# MCU_A_ESP32-WROOM-32U.net
KiCad netlist of a schematic drawn in Altium Designer
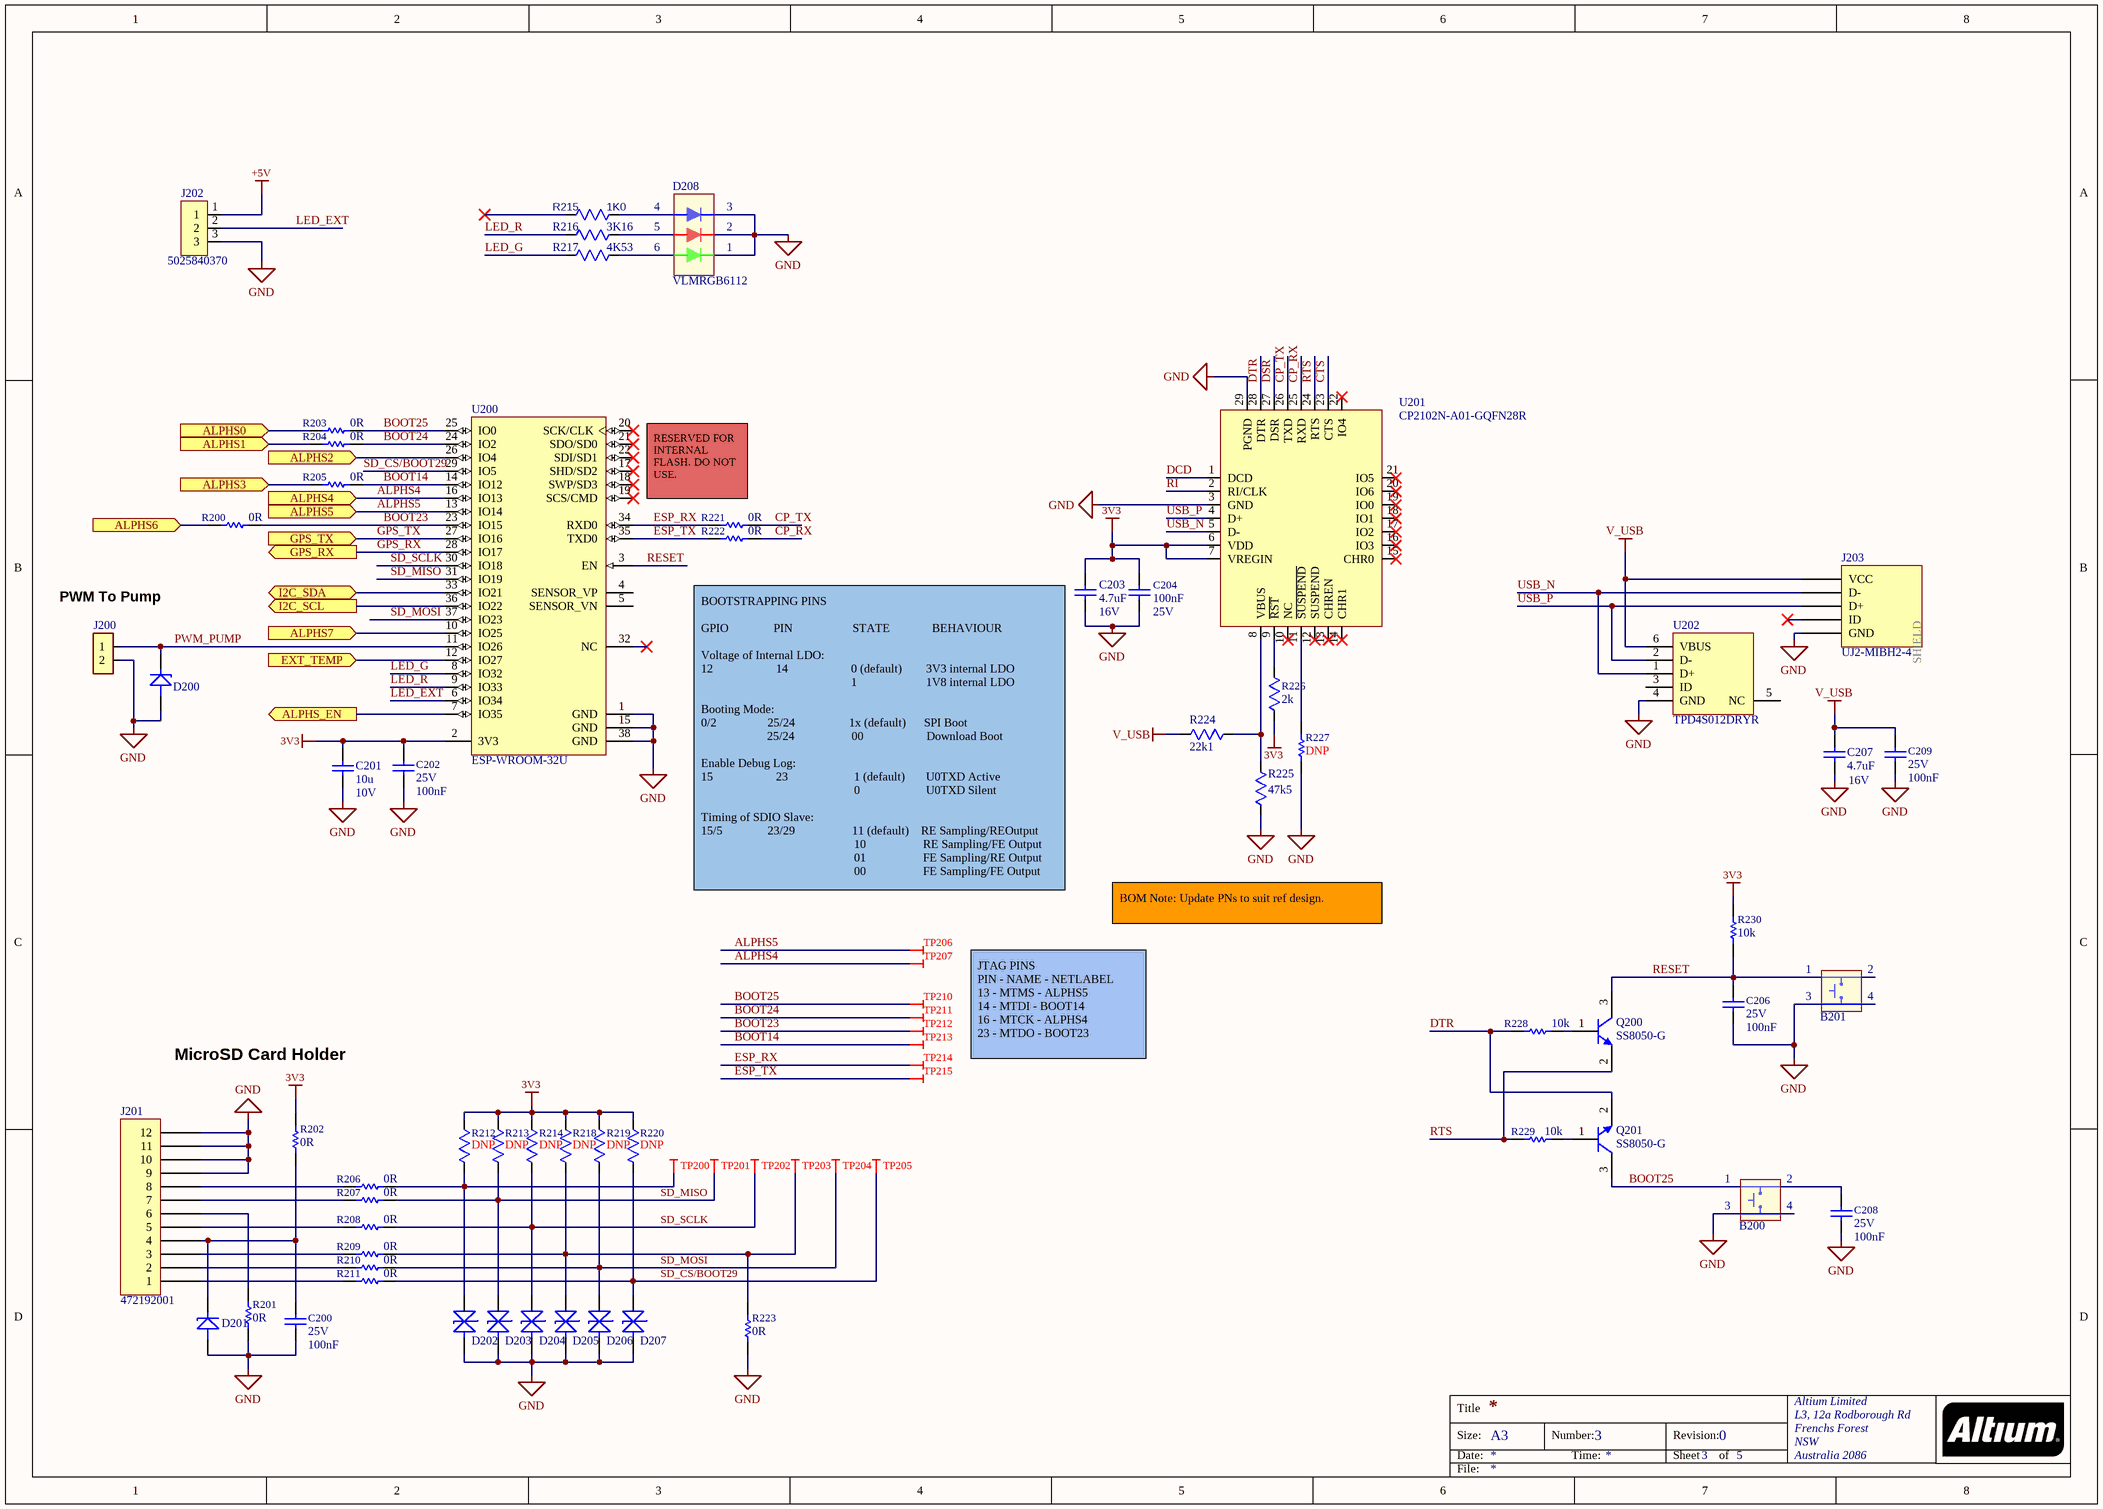
[diagram p0: MCU A ESP32-WROOM-32U.SchDoc]

(export (version "E")
  (design (tool "Eeschema 10.0.6"))
  (components
    (comp (ref "B200")
      (value "Button C&K PTS815 SJG 250 SMTR LFS")
      (footprint "PTS 815")
      (description "Push Button Top")
      (fields
        (field (name "MANUFACTURER") "C&K Components")
        (field (name "MANUFACTURER PART NUMBER") "PTS815 SJG 250 SMTR LFS")
      )
      (libsource (lib "Connectors") (part "Button C&K PTS815 SJG 250 SMTR LFS"))
    )
    (comp (ref "B201")
      (value "Button C&K PTS815 SJG 250 SMTR LFS")
      (footprint "PTS 815")
      (description "Push Button Top")
      (fields
        (field (name "MANUFACTURER") "C&K Components")
        (field (name "MANUFACTURER PART NUMBER") "PTS815 SJG 250 SMTR LFS")
      )
      (libsource (lib "Connectors") (part "Button C&K PTS815 SJG 250 SMTR LFS"))
    )
    (comp (ref "C200")
      (value "100nF")
      (footprint "CAPC1005X06N")
      (fields
        (field (name "VOLTAGE") "25V")
        (field (name "MANUFACTURER PART NUMBER") "CL05A104KA5NNNC")
        (field (name "MANUFACTURER") "Samsung")
        (field (name "Comment") "4.7uF")
      )
      (libsource (lib "Capacitors") (part "4.7uF_0603_10V"))
    )
    (comp (ref "C201")
      (value "10u")
      (footprint "CAPC1005X06N")
      (description "Capacitor")
      (fields
        (field (name "MANUFACTURER PART NUMBER") "CL05A106MP8NUB8")
        (field (name "MANUFACTURER") "Samsung")
        (field (name "VOLTAGE") "10V")
      )
      (libsource (lib "Santuary") (part "CAP{colon} GENERAL"))
    )
    (comp (ref "C202")
      (value "100nF")
      (footprint "CAPC1005X06N")
      (fields
        (field (name "VOLTAGE") "25V")
        (field (name "MANUFACTURER PART NUMBER") "CL05A104KA5NNNC")
        (field (name "MANUFACTURER") "Samsung")
        (field (name "Comment") "4.7uF")
      )
      (libsource (lib "Capacitors") (part "4.7uF_0603_10V"))
    )
    (comp (ref "C203")
      (value "4.7uF")
      (footprint "C1005[0402]")
      (description "Cap,4.7uF,10V,20%,X5R,0402")
      (fields
        (field (name "MANUFACTURER") "Samsung Electro-Mechanics")
        (field (name "MANUFACTURER PART NUMBER") "CL05A475MO5NUNC")
        (field (name "VOLTAGE") "16V")
      )
      (libsource (lib "Capacitors") (part "4.7uF_0402_10V"))
    )
    (comp (ref "C204")
      (value "100nF")
      (footprint "CAPC1005X06N")
      (fields
        (field (name "VOLTAGE") "25V")
        (field (name "MANUFACTURER PART NUMBER") "CL05A104KA5NNNC")
        (field (name "MANUFACTURER") "Samsung")
        (field (name "Comment") "4.7uF")
      )
      (libsource (lib "Capacitors") (part "4.7uF_0603_10V"))
    )
    (comp (ref "C206")
      (value "100nF")
      (footprint "CAPC1005X06N")
      (fields
        (field (name "VOLTAGE") "25V")
        (field (name "MANUFACTURER PART NUMBER") "CL05A104KA5NNNC")
        (field (name "MANUFACTURER") "Samsung")
        (field (name "Comment") "4.7uF")
      )
      (libsource (lib "Capacitors") (part "4.7uF_0603_10V"))
    )
    (comp (ref "C207")
      (value "4.7uF")
      (footprint "C1005[0402]")
      (description "Cap,4.7uF,10V,20%,X5R,0402")
      (fields
        (field (name "MANUFACTURER") "Samsung Electro-Mechanics")
        (field (name "MANUFACTURER PART NUMBER") "CL05A475MO5NUNC")
        (field (name "VOLTAGE") "16V")
      )
      (libsource (lib "Capacitors") (part "4.7uF_0402_10V"))
    )
    (comp (ref "C208")
      (value "100nF")
      (footprint "CAPC1005X06N")
      (fields
        (field (name "VOLTAGE") "25V")
        (field (name "MANUFACTURER PART NUMBER") "CL05A104KA5NNNC")
        (field (name "MANUFACTURER") "Samsung")
        (field (name "Comment") "4.7uF")
      )
      (libsource (lib "Capacitors") (part "4.7uF_0603_10V"))
    )
    (comp (ref "C209")
      (value "100nF")
      (footprint "CAPC1005X06N")
      (fields
        (field (name "VOLTAGE") "25V")
        (field (name "MANUFACTURER PART NUMBER") "CL05A104KA5NNNC")
        (field (name "MANUFACTURER") "Samsung")
        (field (name "Comment") "4.7uF")
      )
      (libsource (lib "Capacitors") (part "4.7uF_0603_10V"))
    )
    (comp (ref "D200")
      (value "3.3V TVS")
      (footprint "NXP PTVSxS1UR-Series (SOD123W)")
      (fields
        (field (name "MANUFACTURER") "Nexperia")
        (field (name "MANUFACTURER PART NUMBER") "PTVS3V3S1UTR,115")
      )
      (libsource (lib "FSM_2018") (part "NXP PTVSxS1UR-Series"))
    )
    (comp (ref "D201")
      (value "3.3V TVS")
      (footprint "NXP PTVSxS1UR-Series (SOD123W)")
      (fields
        (field (name "MANUFACTURER") "Nexperia")
        (field (name "MANUFACTURER PART NUMBER") "PTVS3V3S1UTR,115")
      )
      (libsource (lib "FSM_2018") (part "NXP PTVSxS1UR-Series"))
    )
    (comp (ref "D202")
      (value "ESD7951ST5GOSCT-ND")
      (footprint "SODFL100X40-2N")
      (description "TVS Diode")
      (fields
        (field (name "MANUFACTURER PART NUMBER") "ESD7951ST5G")
        (field (name "MANUFACTURER") "ON Semiconductor")
      )
      (libsource (lib "Gas Monitor Components") (part "ESD7951S"))
    )
    (comp (ref "D203")
      (value "ESD7951ST5GOSCT-ND")
      (footprint "SODFL100X40-2N")
      (description "TVS Diode")
      (fields
        (field (name "MANUFACTURER PART NUMBER") "ESD7951ST5G")
        (field (name "MANUFACTURER") "ON Semiconductor")
      )
      (libsource (lib "Gas Monitor Components") (part "ESD7951S"))
    )
    (comp (ref "D204")
      (value "ESD7951ST5GOSCT-ND")
      (footprint "SODFL100X40-2N")
      (description "TVS Diode")
      (fields
        (field (name "MANUFACTURER PART NUMBER") "ESD7951ST5G")
        (field (name "MANUFACTURER") "ON Semiconductor")
      )
      (libsource (lib "Gas Monitor Components") (part "ESD7951S"))
    )
    (comp (ref "D205")
      (value "ESD7951ST5GOSCT-ND")
      (footprint "SODFL100X40-2N")
      (description "TVS Diode")
      (fields
        (field (name "MANUFACTURER PART NUMBER") "ESD7951ST5G")
        (field (name "MANUFACTURER") "ON Semiconductor")
      )
      (libsource (lib "Gas Monitor Components") (part "ESD7951S"))
    )
    (comp (ref "D206")
      (value "ESD7951ST5GOSCT-ND")
      (footprint "SODFL100X40-2N")
      (description "TVS Diode")
      (fields
        (field (name "MANUFACTURER PART NUMBER") "ESD7951ST5G")
        (field (name "MANUFACTURER") "ON Semiconductor")
      )
      (libsource (lib "Gas Monitor Components") (part "ESD7951S"))
    )
    (comp (ref "D207")
      (value "ESD7951ST5GOSCT-ND")
      (footprint "SODFL100X40-2N")
      (description "TVS Diode")
      (fields
        (field (name "MANUFACTURER PART NUMBER") "ESD7951ST5G")
        (field (name "MANUFACTURER") "ON Semiconductor")
      )
      (libsource (lib "Gas Monitor Components") (part "ESD7951S"))
    )
    (comp (ref "D208")
      (value "VLMRGB6112")
      (footprint "VLMRGB6112")
      (description "LED RGB Clear 624nm/526nm/469nm 2V/3.1V/3V PLCC-6")
      (fields
        (field (name "MANUFACTURER") "Vishay Semiconductor Opto Division")
        (field (name "MANUFACTURER PART NUMBER") "VLMRGB6112-00-GS08")
      )
      (libsource (lib "LEDs") (part "VLMRGB6112"))
    )
    (comp (ref "J200")
      (value "PWM To Pump")
      (footprint "6410/2pin")
      (description "Connector 2 pin")
      (fields (field (name "MANUFACTURER") "Molex") (field (name "MANUFACTURER PART NUMBER") "0022232023"))
      (libsource (lib "VolcDB") (part "CON2"))
    )
    (comp (ref "J201")
      (value "472192001")
      (footprint "SD-47219-001")
      (fields (field (name "MANUFACTURER") "Molex") (field (name "MANUFACTURER PART NUMBER") "0472192001"))
      (libsource (lib "Gas Monitor Components") (part "CON12"))
    )
    (comp (ref "J202")
      (value "5025840370")
      (footprint "502584-0370")
      (fields (field (name "MANUFACTURER") "Molex"))
      (libsource (lib "Sora") (part "CONN{colon} 3x1"))
    )
    (comp (ref "J203")
      (value "UJ2-MIBH2-4")
      (footprint "UJ2-MIBH2-4-SMT")
      (fields
        (field (name "MANUFACTURER") "CUI")
        (field (name "MANUFACTURER PART NUMBER") "UJ2-MIBH2-4-SMT-TR")
      )
      (libsource (lib "Gas Monitor Components") (part "USB Shield"))
    )
    (comp (ref "Q200")
      (value "SS8050-G")
      (footprint "ONSC-SOT-23-3-318-08_V")
      (description "General Purpose Transistor, NPN Silicon, 3-Pin SOT-23, Tape and Reel")
      (fields (field (name "MANUFACTURER") "Comchip Technology"))
      (libsource (lib "Altium Content Vault") (part "ONSC-NPN-B1E2C3-3"))
    )
    (comp (ref "Q201")
      (value "SS8050-G")
      (footprint "ONSC-SOT-23-3-318-08_V")
      (description "General Purpose Transistor, NPN Silicon, 3-Pin SOT-23, Tape and Reel")
      (fields (field (name "MANUFACTURER") "Comchip Technology"))
      (libsource (lib "Altium Content Vault") (part "ONSC-NPN-B1E2C3-3"))
    )
    (comp (ref "R200")
      (value "0R")
      (footprint "RESC1005X03N")
      (fields
        (field (name "MANUFACTURER") "Panasonic")
        (field (name "MANUFACTURER PART NUMBER") "ERJ-2GE0R00X")
        (field (name "Comment") "RES: GENERAL")
      )
      (libsource (lib "Santuary") (part "RES{colon} GENERAL"))
    )
    (comp (ref "R201")
      (value "0R")
      (footprint "RESC1005X03N")
      (fields
        (field (name "MANUFACTURER") "Panasonic")
        (field (name "MANUFACTURER PART NUMBER") "ERJ-2GE0R00X")
        (field (name "Comment") "RES: GENERAL")
      )
      (libsource (lib "Santuary") (part "RES{colon} GENERAL"))
    )
    (comp (ref "R202")
      (value "0R")
      (footprint "RESC1005X03N")
      (fields
        (field (name "MANUFACTURER") "Panasonic")
        (field (name "MANUFACTURER PART NUMBER") "ERJ-2GE0R00X")
        (field (name "Comment") "RES: GENERAL")
      )
      (libsource (lib "Santuary") (part "RES{colon} GENERAL"))
    )
    (comp (ref "R203")
      (value "0R")
      (footprint "RESC1005X03N")
      (fields
        (field (name "MANUFACTURER") "Panasonic")
        (field (name "MANUFACTURER PART NUMBER") "ERJ-2GE0R00X")
        (field (name "Comment") "RES: GENERAL")
      )
      (libsource (lib "Santuary") (part "RES{colon} GENERAL"))
    )
    (comp (ref "R204")
      (value "0R")
      (footprint "RESC1005X03N")
      (fields
        (field (name "MANUFACTURER") "Panasonic")
        (field (name "MANUFACTURER PART NUMBER") "ERJ-2GE0R00X")
        (field (name "Comment") "RES: GENERAL")
      )
      (libsource (lib "Santuary") (part "RES{colon} GENERAL"))
    )
    (comp (ref "R205")
      (value "0R")
      (footprint "RESC1005X03N")
      (fields
        (field (name "MANUFACTURER") "Panasonic")
        (field (name "MANUFACTURER PART NUMBER") "ERJ-2GE0R00X")
        (field (name "Comment") "RES: GENERAL")
      )
      (libsource (lib "Santuary") (part "RES{colon} GENERAL"))
    )
    (comp (ref "R206")
      (value "0R")
      (footprint "RESC1005X03N")
      (fields
        (field (name "MANUFACTURER") "Panasonic")
        (field (name "MANUFACTURER PART NUMBER") "ERJ-2GE0R00X")
        (field (name "Comment") "RES: GENERAL")
      )
      (libsource (lib "Santuary") (part "RES{colon} GENERAL"))
    )
    (comp (ref "R207")
      (value "0R")
      (footprint "RESC1005X03N")
      (fields
        (field (name "MANUFACTURER") "Panasonic")
        (field (name "MANUFACTURER PART NUMBER") "ERJ-2GE0R00X")
        (field (name "Comment") "RES: GENERAL")
      )
      (libsource (lib "Santuary") (part "RES{colon} GENERAL"))
    )
    (comp (ref "R208")
      (value "0R")
      (footprint "RESC1005X03N")
      (fields
        (field (name "MANUFACTURER") "Panasonic")
        (field (name "MANUFACTURER PART NUMBER") "ERJ-2GE0R00X")
        (field (name "Comment") "RES: GENERAL")
      )
      (libsource (lib "Santuary") (part "RES{colon} GENERAL"))
    )
    (comp (ref "R209")
      (value "0R")
      (footprint "RESC1005X03N")
      (fields
        (field (name "MANUFACTURER") "Panasonic")
        (field (name "MANUFACTURER PART NUMBER") "ERJ-2GE0R00X")
        (field (name "Comment") "RES: GENERAL")
      )
      (libsource (lib "Santuary") (part "RES{colon} GENERAL"))
    )
    (comp (ref "R210")
      (value "0R")
      (footprint "RESC1005X03N")
      (fields
        (field (name "MANUFACTURER") "Panasonic")
        (field (name "MANUFACTURER PART NUMBER") "ERJ-2GE0R00X")
        (field (name "Comment") "RES: GENERAL")
      )
      (libsource (lib "Santuary") (part "RES{colon} GENERAL"))
    )
    (comp (ref "R211")
      (value "0R")
      (footprint "RESC1005X03N")
      (fields
        (field (name "MANUFACTURER") "Panasonic")
        (field (name "MANUFACTURER PART NUMBER") "ERJ-2GE0R00X")
        (field (name "Comment") "RES: GENERAL")
      )
      (libsource (lib "Santuary") (part "RES{colon} GENERAL"))
    )
    (comp (ref "R212")
      (value "DNP")
      (footprint "RESC1005X03N")
      (description "RES 1K Ohm ±5%, 0.25W,1/4W 0603")
      (fields (field (name "Comment") "10K"))
      (libsource (lib "Resistors") (part "1K00_0603_0.1W"))
    )
    (comp (ref "R213")
      (value "DNP")
      (footprint "RESC1005X03N")
      (description "RES 1K Ohm ±5%, 0.25W,1/4W 0603")
      (fields (field (name "Comment") "10K"))
      (libsource (lib "Resistors") (part "1K00_0603_0.1W"))
    )
    (comp (ref "R214")
      (value "DNP")
      (footprint "RESC1005X03N")
      (description "RES 1K Ohm ±5%, 0.25W,1/4W 0603")
      (fields (field (name "Comment") "10K"))
      (libsource (lib "Resistors") (part "1K00_0603_0.1W"))
    )
    (comp (ref "R215")
      (value "1K0")
      (footprint "R1608[0603] small")
      (description "RES 1K Ohm ±5%, 0.25W,1/4W 0603")
      (fields (field (name "MANUFACTURER") "Rohm") (field (name "MANUFACTURER PART NUMBER") "ESR03EZPJ102"))
      (libsource (lib "Resistors") (part "1K00_0603_0.1W"))
    )
    (comp (ref "R216")
      (value "3K16")
      (footprint "R1608[0603] small")
      (description "Res,SMD,1/10W,3K16,0603,1%")
      (fields
        (field (name "MANUFACTURER") "Stackpole Electronics")
        (field (name "MANUFACTURER PART NUMBER") "RMCF0603FT3K16")
      )
      (libsource (lib "Resistors") (part "3K16_Resistor_0603"))
    )
    (comp (ref "R217")
      (value "4K53")
      (footprint "R1608[0603] small")
      (description "Res,SMD,4K53,1/10W,1%,0603")
      (fields
        (field (name "MANUFACTURER") "Yageo")
        (field (name "MANUFACTURER PART NUMBER") "RC0603FR-074K53L")
      )
      (libsource (lib "Resistors") (part "4K53_Resistor_0603"))
    )
    (comp (ref "R218")
      (value "DNP")
      (footprint "RESC1005X03N")
      (description "RES 1K Ohm ±5%, 0.25W,1/4W 0603")
      (fields (field (name "Comment") "10K"))
      (libsource (lib "Resistors") (part "1K00_0603_0.1W"))
    )
    (comp (ref "R219")
      (value "DNP")
      (footprint "RESC1005X03N")
      (description "RES 1K Ohm ±5%, 0.25W,1/4W 0603")
      (fields (field (name "Comment") "10K"))
      (libsource (lib "Resistors") (part "1K00_0603_0.1W"))
    )
    (comp (ref "R220")
      (value "DNP")
      (footprint "RESC1005X03N")
      (description "RES 1K Ohm ±5%, 0.25W,1/4W 0603")
      (fields (field (name "Comment") "10K"))
      (libsource (lib "Resistors") (part "1K00_0603_0.1W"))
    )
    (comp (ref "R221")
      (value "0R")
      (footprint "RESC1005X03N")
      (fields
        (field (name "MANUFACTURER") "Panasonic")
        (field (name "MANUFACTURER PART NUMBER") "ERJ-2GE0R00X")
        (field (name "Comment") "RES: GENERAL")
      )
      (libsource (lib "Santuary") (part "RES{colon} GENERAL"))
    )
    (comp (ref "R222")
      (value "0R")
      (footprint "RESC1005X03N")
      (fields
        (field (name "MANUFACTURER") "Panasonic")
        (field (name "MANUFACTURER PART NUMBER") "ERJ-2GE0R00X")
        (field (name "Comment") "RES: GENERAL")
      )
      (libsource (lib "Santuary") (part "RES{colon} GENERAL"))
    )
    (comp (ref "R223")
      (value "0R")
      (footprint "RESC1005X03N")
      (fields
        (field (name "MANUFACTURER") "Panasonic")
        (field (name "MANUFACTURER PART NUMBER") "ERJ-2GE0R00X")
        (field (name "Comment") "RES: GENERAL")
      )
      (libsource (lib "Santuary") (part "RES{colon} GENERAL"))
    )
    (comp (ref "R224")
      (value "22k1")
      (footprint "R1005[0402]")
      (description "Res,SMD,22k,0603,5%,1/4W")
      (fields
        (field (name "MANUFACTURER PART NUMBER") "ERJ-2RKF2212X")
        (field (name "MANUFACTURER") "Panasonic")
      )
      (libsource (lib "Resistors") (part "22K_0603_1/4W"))
    )
    (comp (ref "R225")
      (value "47k5")
      (footprint "R1005[0402]")
      (description "Res,SMD,22k,0603,5%,1/4W")
      (fields
        (field (name "MANUFACTURER PART NUMBER") "ERJ-2RKF4752X")
        (field (name "MANUFACTURER") "Panasonic")
      )
      (libsource (lib "Resistors") (part "22K_0603_1/4W"))
    )
    (comp (ref "R226")
      (value "2k")
      (footprint "R1005[0402]")
      (fields
        (field (name "MANUFACTURER") "Panasonic")
        (field (name "MANUFACTURER PART NUMBER") "ERJ-2RKF2001X")
        (field (name "Comment") "10K")
      )
      (libsource (lib "Resistors") (part "1K00_0603_0.1W"))
    )
    (comp (ref "R227")
      (value "DNP")
      (footprint "RESC1005X03N")
      (fields (field (name "Comment") "RES: GENERAL"))
      (libsource (lib "Santuary") (part "RES{colon} GENERAL"))
    )
    (comp (ref "R228")
      (value "10k")
      (footprint "RESC1005X03N")
      (fields
        (field (name "MANUFACTURER") "Panasonic")
        (field (name "MANUFACTURER PART NUMBER") "ERJ-2RKF1002X")
        (field (name "Comment") "RES: GENERAL")
      )
      (libsource (lib "Santuary") (part "RES{colon} GENERAL"))
    )
    (comp (ref "R229")
      (value "10k")
      (footprint "RESC1005X03N")
      (fields
        (field (name "MANUFACTURER") "Panasonic")
        (field (name "MANUFACTURER PART NUMBER") "ERJ-2RKF1002X")
        (field (name "Comment") "RES: GENERAL")
      )
      (libsource (lib "Santuary") (part "RES{colon} GENERAL"))
    )
    (comp (ref "R230")
      (value "10k")
      (footprint "RESC1005X03N")
      (fields
        (field (name "MANUFACTURER") "Panasonic")
        (field (name "MANUFACTURER PART NUMBER") "ERJ-2RKF1002X")
        (field (name "Comment") "RES: GENERAL")
      )
      (libsource (lib "Santuary") (part "RES{colon} GENERAL"))
    )
    (comp (ref "TP200")
      (value "PAD")
      (footprint "TP_SMD_39MIL")
      (description "SMD Test Pad")
      (fields (field (name "MANUFACTURER") "No P/N Required"))
      (libsource (lib "Connectors") (part "TP_SMD_39MIL"))
    )
    (comp (ref "TP201")
      (value "PAD")
      (footprint "TP_SMD_39MIL")
      (description "SMD Test Pad")
      (fields (field (name "MANUFACTURER") "No P/N Required"))
      (libsource (lib "Connectors") (part "TP_SMD_39MIL"))
    )
    (comp (ref "TP202")
      (value "PAD")
      (footprint "TP_SMD_39MIL")
      (description "SMD Test Pad")
      (fields (field (name "MANUFACTURER") "No P/N Required"))
      (libsource (lib "Connectors") (part "TP_SMD_39MIL"))
    )
    (comp (ref "TP203")
      (value "PAD")
      (footprint "TP_SMD_39MIL")
      (description "SMD Test Pad")
      (fields (field (name "MANUFACTURER") "No P/N Required"))
      (libsource (lib "Connectors") (part "TP_SMD_39MIL"))
    )
    (comp (ref "TP204")
      (value "PAD")
      (footprint "TP_SMD_39MIL")
      (description "SMD Test Pad")
      (fields (field (name "MANUFACTURER") "No P/N Required"))
      (libsource (lib "Connectors") (part "TP_SMD_39MIL"))
    )
    (comp (ref "TP205")
      (value "PAD")
      (footprint "TP_SMD_39MIL")
      (description "SMD Test Pad")
      (fields (field (name "MANUFACTURER") "No P/N Required"))
      (libsource (lib "Connectors") (part "TP_SMD_39MIL"))
    )
    (comp (ref "TP206")
      (value "PAD")
      (footprint "TP_SMD_39MIL")
      (description "SMD Test Pad")
      (fields (field (name "MANUFACTURER") "No P/N Required"))
      (libsource (lib "Connectors") (part "TP_SMD_39MIL"))
    )
    (comp (ref "TP207")
      (value "PAD")
      (footprint "TP_SMD_39MIL")
      (description "SMD Test Pad")
      (fields (field (name "MANUFACTURER") "No P/N Required"))
      (libsource (lib "Connectors") (part "TP_SMD_39MIL"))
    )
    (comp (ref "TP210")
      (value "PAD")
      (footprint "TP_SMD_39MIL")
      (description "SMD Test Pad")
      (fields (field (name "MANUFACTURER") "No P/N Required"))
      (libsource (lib "Connectors") (part "TP_SMD_39MIL"))
    )
    (comp (ref "TP211")
      (value "PAD")
      (footprint "TP_SMD_39MIL")
      (description "SMD Test Pad")
      (fields (field (name "MANUFACTURER") "No P/N Required"))
      (libsource (lib "Connectors") (part "TP_SMD_39MIL"))
    )
    (comp (ref "TP212")
      (value "PAD")
      (footprint "TP_SMD_39MIL")
      (description "SMD Test Pad")
      (fields (field (name "MANUFACTURER") "No P/N Required"))
      (libsource (lib "Connectors") (part "TP_SMD_39MIL"))
    )
    (comp (ref "TP213")
      (value "PAD")
      (footprint "TP_SMD_39MIL")
      (description "SMD Test Pad")
      (fields (field (name "MANUFACTURER") "No P/N Required"))
      (libsource (lib "Connectors") (part "TP_SMD_39MIL"))
    )
    (comp (ref "TP214")
      (value "PAD")
      (footprint "TP_SMD_39MIL")
      (description "SMD Test Pad")
      (fields (field (name "MANUFACTURER") "No P/N Required"))
      (libsource (lib "Connectors") (part "TP_SMD_39MIL"))
    )
    (comp (ref "TP215")
      (value "PAD")
      (footprint "TP_SMD_39MIL")
      (description "SMD Test Pad")
      (fields (field (name "MANUFACTURER") "No P/N Required"))
      (libsource (lib "Connectors") (part "TP_SMD_39MIL"))
    )
    (comp (ref "U200")
      (value "ESP-WROOM-32U")
      (footprint "OLMX-ESP-WROOM-32")
      (description "Espressif System, 2.7 to 3.6 V, -40 to 85 degC, 38-Pin SMD")
      (fields
        (field (name "MANUFACTURER") "Espressif Systems")
        (field (name "MANUFACTURER PART NUMBER") "ESP32-WROOM-32U")
      )
      (libsource (lib "Altium Content Vault") (part "OLMX-ESP-WROOM-32-38"))
    )
    (comp (ref "U201")
      (value "CP2102N-A01-GQFN28R")
      (footprint "QFN50P500X500X80_HS-29N")
      (description "USB to UART converter")
      (fields (field (name "MANUFACTURER") "Silicon Labs"))
      (libsource (lib "ICs-V") (part "CP2102N QFN28"))
    )
    (comp (ref "U202")
      (value "TPD4S012DRYR")
      (footprint "DRY0006A")
      (fields (field (name "MANUFACTURER") "Texas Instruments"))
      (libsource (lib "Altium Content Vault") (part "TI-TPD4S012-SON_DRY-6"))
    )
  )
  (nets
    (net (code "1") (name "+5V") (class "Default")
      (node (ref "J202") (pin "1") (pinfunction "1_1") (pintype "passive"))
    )
    (net (code "2") (name "/ALPHS0") (class "Default")
      (node (ref "R203") (pin "2") (pinfunction "2_2") (pintype "passive"))
    )
    (net (code "3") (name "/ALPHS1") (class "Default")
      (node (ref "R204") (pin "2") (pinfunction "2_2") (pintype "passive"))
    )
    (net (code "4") (name "/ALPHS2") (class "Default")
      (node (ref "U200") (pin "26") (pinfunction "IO4_26") (pintype "bidirectional"))
    )
    (net (code "5") (name "/ALPHS3") (class "Default")
      (node (ref "R205") (pin "2") (pinfunction "2_2") (pintype "passive"))
    )
    (net (code "6") (name "/ALPHS4") (class "Default")
      (node (ref "TP207") (pin "1") (pintype "passive"))
      (node (ref "U200") (pin "16") (pinfunction "IO13_16") (pintype "bidirectional"))
    )
    (net (code "7") (name "/ALPHS5") (class "Default")
      (node (ref "TP206") (pin "1") (pintype "passive"))
      (node (ref "U200") (pin "13") (pinfunction "IO14_13") (pintype "bidirectional"))
    )
    (net (code "8") (name "/ALPHS6") (class "Default")
      (node (ref "R200") (pin "2") (pinfunction "2_2") (pintype "passive"))
    )
    (net (code "9") (name "/ALPHS7") (class "Default")
      (node (ref "U200") (pin "10") (pinfunction "IO25_10") (pintype "bidirectional"))
    )
    (net (code "10") (name "/ALPHS_EN") (class "Default")
      (node (ref "U200") (pin "7") (pinfunction "IO35_7") (pintype "bidirectional"))
    )
    (net (code "11") (name "/BOOT14") (class "Default")
      (node (ref "R205") (pin "1") (pinfunction "1_1") (pintype "passive"))
      (node (ref "TP213") (pin "1") (pintype "passive"))
      (node (ref "U200") (pin "14") (pinfunction "IO12_14") (pintype "bidirectional"))
    )
    (net (code "12") (name "/BOOT23") (class "Default")
      (node (ref "R200") (pin "1") (pinfunction "1_1") (pintype "passive"))
      (node (ref "TP212") (pin "1") (pintype "passive"))
      (node (ref "U200") (pin "23") (pinfunction "IO15_23") (pintype "bidirectional"))
    )
    (net (code "13") (name "/BOOT24") (class "Default")
      (node (ref "R204") (pin "1") (pinfunction "1_1") (pintype "passive"))
      (node (ref "TP211") (pin "1") (pintype "passive"))
      (node (ref "U200") (pin "24") (pinfunction "IO2_24") (pintype "bidirectional"))
    )
    (net (code "14") (name "/BOOT25") (class "Default")
      (node (ref "B200") (pin "1") (pinfunction "1_1") (pintype "passive"))
      (node (ref "Q201") (pin "3") (pinfunction "C_3") (pintype "passive"))
      (node (ref "R203") (pin "1") (pinfunction "1_1") (pintype "passive"))
      (node (ref "TP210") (pin "1") (pintype "passive"))
      (node (ref "U200") (pin "25") (pinfunction "IO0_25") (pintype "bidirectional"))
    )
    (net (code "15") (name "/CP_RX") (class "Default")
      (node (ref "R222") (pin "1") (pinfunction "1_1") (pintype "passive"))
      (node (ref "U201") (pin "25") (pinfunction "RXD_25") (pintype "passive"))
    )
    (net (code "16") (name "/CP_TX") (class "Default")
      (node (ref "R221") (pin "1") (pinfunction "1_1") (pintype "passive"))
      (node (ref "U201") (pin "26") (pinfunction "TXD_26") (pintype "passive"))
    )
    (net (code "17") (name "/CTS") (class "Default")
      (node (ref "U201") (pin "23") (pinfunction "CTS_23") (pintype "passive"))
    )
    (net (code "18") (name "/DCD") (class "Default")
      (node (ref "U201") (pin "1") (pinfunction "DCD_1") (pintype "passive"))
    )
    (net (code "19") (name "/DSR") (class "Default")
      (node (ref "U201") (pin "27") (pinfunction "DSR_27") (pintype "passive"))
    )
    (net (code "20") (name "/DTR") (class "Default")
      (node (ref "Q201") (pin "2") (pinfunction "E_2") (pintype "passive"))
      (node (ref "R228") (pin "2") (pinfunction "2_2") (pintype "passive"))
      (node (ref "U201") (pin "28") (pinfunction "DTR_28") (pintype "passive"))
    )
    (net (code "21") (name "/ESP_RX") (class "Default")
      (node (ref "R221") (pin "2") (pinfunction "2_2") (pintype "passive"))
      (node (ref "TP214") (pin "1") (pintype "passive"))
      (node (ref "U200") (pin "34") (pinfunction "RXD0_34") (pintype "bidirectional"))
    )
    (net (code "22") (name "/ESP_TX") (class "Default")
      (node (ref "R222") (pin "2") (pinfunction "2_2") (pintype "passive"))
      (node (ref "TP215") (pin "1") (pintype "passive"))
      (node (ref "U200") (pin "35") (pinfunction "TXD0_35") (pintype "bidirectional"))
    )
    (net (code "23") (name "/EXT_TEMP") (class "Default")
      (node (ref "U200") (pin "12") (pinfunction "IO27_12") (pintype "bidirectional"))
    )
    (net (code "24") (name "/GPS_RX") (class "Default")
      (node (ref "U200") (pin "28") (pinfunction "IO17_28") (pintype "bidirectional"))
    )
    (net (code "25") (name "/GPS_TX") (class "Default")
      (node (ref "U200") (pin "27") (pinfunction "IO16_27") (pintype "bidirectional"))
    )
    (net (code "26") (name "/I2C_SCL") (class "Default")
      (node (ref "U200") (pin "36") (pinfunction "IO22_36") (pintype "bidirectional"))
    )
    (net (code "27") (name "/I2C_SDA") (class "Default")
      (node (ref "U200") (pin "33") (pinfunction "IO21_33") (pintype "bidirectional"))
    )
    (net (code "28") (name "/LED_EXT") (class "Default")
      (node (ref "J202") (pin "2") (pinfunction "2_2") (pintype "passive"))
      (node (ref "U200") (pin "6") (pinfunction "IO34_6") (pintype "bidirectional"))
    )
    (net (code "29") (name "/LED_G") (class "Default")
      (node (ref "R217") (pin "1") (pintype "passive"))
      (node (ref "U200") (pin "8") (pinfunction "IO32_8") (pintype "bidirectional"))
    )
    (net (code "30") (name "/LED_R") (class "Default")
      (node (ref "R216") (pin "1") (pintype "passive"))
      (node (ref "U200") (pin "9") (pinfunction "IO33_9") (pintype "bidirectional"))
    )
    (net (code "31") (name "/PWM_PUMP") (class "Default")
      (node (ref "D200") (pin "1") (pinfunction "1_1") (pintype "passive"))
      (node (ref "J200") (pin "1") (pinfunction "1_1") (pintype "passive"))
      (node (ref "U200") (pin "11") (pinfunction "IO26_11") (pintype "bidirectional"))
    )
    (net (code "32") (name "/RESET") (class "Default")
      (node (ref "B201") (pin "1") (pinfunction "1_1") (pintype "passive"))
      (node (ref "C206") (pin "1") (pintype "passive"))
      (node (ref "Q200") (pin "3") (pinfunction "C_3") (pintype "passive"))
      (node (ref "R230") (pin "2") (pinfunction "2_2") (pintype "passive"))
      (node (ref "U200") (pin "3") (pinfunction "EN_3") (pintype "input"))
    )
    (net (code "33") (name "/RI") (class "Default")
      (node (ref "U201") (pin "2") (pinfunction "RI/CLK_2") (pintype "passive"))
    )
    (net (code "34") (name "/RTS") (class "Default")
      (node (ref "Q200") (pin "2") (pinfunction "E_2") (pintype "passive"))
      (node (ref "R229") (pin "2") (pinfunction "2_2") (pintype "passive"))
      (node (ref "U201") (pin "24") (pinfunction "RTS_24") (pintype "passive"))
    )
    (net (code "35") (name "/SD_CS{slash}BOOT29") (class "Default")
      (node (ref "D207") (pin "2") (pinfunction "ANODE_2") (pintype "passive"))
      (node (ref "R211") (pin "1") (pinfunction "1_1") (pintype "passive"))
      (node (ref "R220") (pin "1") (pintype "passive"))
      (node (ref "TP205") (pin "1") (pintype "passive"))
      (node (ref "U200") (pin "29") (pinfunction "IO5_29") (pintype "bidirectional"))
    )
    (net (code "36") (name "/SD_MISO") (class "Default")
      (node (ref "D203") (pin "2") (pinfunction "ANODE_2") (pintype "passive"))
      (node (ref "R207") (pin "1") (pinfunction "1_1") (pintype "passive"))
      (node (ref "R213") (pin "1") (pintype "passive"))
      (node (ref "TP201") (pin "1") (pintype "passive"))
      (node (ref "U200") (pin "31") (pinfunction "IO19_31") (pintype "bidirectional"))
    )
    (net (code "37") (name "/SD_MOSI") (class "Default")
      (node (ref "D206") (pin "2") (pinfunction "ANODE_2") (pintype "passive"))
      (node (ref "R210") (pin "1") (pinfunction "1_1") (pintype "passive"))
      (node (ref "R219") (pin "1") (pintype "passive"))
      (node (ref "TP204") (pin "1") (pintype "passive"))
      (node (ref "U200") (pin "37") (pinfunction "IO23_37") (pintype "bidirectional"))
    )
    (net (code "38") (name "/SD_SCLK") (class "Default")
      (node (ref "D204") (pin "2") (pinfunction "ANODE_2") (pintype "passive"))
      (node (ref "R208") (pin "1") (pinfunction "1_1") (pintype "passive"))
      (node (ref "R214") (pin "1") (pintype "passive"))
      (node (ref "TP202") (pin "1") (pintype "passive"))
      (node (ref "U200") (pin "30") (pinfunction "IO18_30") (pintype "bidirectional"))
    )
    (net (code "39") (name "/USB_N") (class "Default")
      (node (ref "J203") (pin "2") (pinfunction "D-_2") (pintype "passive"))
      (node (ref "U201") (pin "5") (pinfunction "D-_5") (pintype "passive"))
      (node (ref "U202") (pin "1") (pinfunction "D+_1") (pintype "passive"))
    )
    (net (code "40") (name "/USB_P") (class "Default")
      (node (ref "J203") (pin "3") (pinfunction "D+_3") (pintype "passive"))
      (node (ref "U201") (pin "4") (pinfunction "D+_4") (pintype "passive"))
      (node (ref "U202") (pin "2") (pinfunction "D-_2") (pintype "passive"))
    )
    (net (code "41") (name "3V3") (class "Default")
      (node (ref "C201") (pin "2") (pinfunction "2_2") (pintype "passive"))
      (node (ref "C202") (pin "1") (pintype "passive"))
      (node (ref "C203") (pin "2") (pintype "passive"))
      (node (ref "C204") (pin "1") (pintype "passive"))
      (node (ref "R202") (pin "1") (pinfunction "1_1") (pintype "passive"))
      (node (ref "R212") (pin "2") (pintype "passive"))
      (node (ref "R213") (pin "2") (pintype "passive"))
      (node (ref "R214") (pin "2") (pintype "passive"))
      (node (ref "R218") (pin "2") (pintype "passive"))
      (node (ref "R219") (pin "2") (pintype "passive"))
      (node (ref "R220") (pin "2") (pintype "passive"))
      (node (ref "R226") (pin "1") (pintype "passive"))
      (node (ref "R230") (pin "1") (pinfunction "1_1") (pintype "passive"))
      (node (ref "U200") (pin "2") (pinfunction "3V3_2") (pintype "power_in"))
      (node (ref "U201") (pin "6") (pinfunction "VDD_6") (pintype "power_in"))
      (node (ref "U201") (pin "7") (pinfunction "VREGIN_7") (pintype "power_in"))
    )
    (net (code "42") (name "GND") (class "Default")
      (node (ref "B200") (pin "3") (pinfunction "3_3") (pintype "passive"))
      (node (ref "B201") (pin "3") (pinfunction "3_3") (pintype "passive"))
      (node (ref "C200") (pin "2") (pintype "passive"))
      (node (ref "C201") (pin "1") (pinfunction "1_1") (pintype "passive"))
      (node (ref "C202") (pin "2") (pintype "passive"))
      (node (ref "C203") (pin "1") (pintype "passive"))
      (node (ref "C204") (pin "2") (pintype "passive"))
      (node (ref "C206") (pin "2") (pintype "passive"))
      (node (ref "C207") (pin "1") (pintype "passive"))
      (node (ref "C208") (pin "2") (pintype "passive"))
      (node (ref "C209") (pin "2") (pintype "passive"))
      (node (ref "D200") (pin "2") (pinfunction "2_2") (pintype "passive"))
      (node (ref "D201") (pin "2") (pinfunction "2_2") (pintype "passive"))
      (node (ref "D202") (pin "1") (pinfunction "CATHODE_1") (pintype "passive"))
      (node (ref "D203") (pin "1") (pinfunction "CATHODE_1") (pintype "passive"))
      (node (ref "D204") (pin "1") (pinfunction "CATHODE_1") (pintype "passive"))
      (node (ref "D205") (pin "1") (pinfunction "CATHODE_1") (pintype "passive"))
      (node (ref "D206") (pin "1") (pinfunction "CATHODE_1") (pintype "passive"))
      (node (ref "D207") (pin "1") (pinfunction "CATHODE_1") (pintype "passive"))
      (node (ref "D208") (pin "1") (pinfunction "A2_1") (pintype "passive"))
      (node (ref "D208") (pin "2") (pinfunction "C3_2") (pintype "passive"))
      (node (ref "D208") (pin "3") (pinfunction "A3_3") (pintype "passive"))
      (node (ref "J200") (pin "2") (pinfunction "2_2") (pintype "passive"))
      (node (ref "J201") (pin "10") (pinfunction "10_10") (pintype "passive"))
      (node (ref "J201") (pin "11") (pinfunction "11_11") (pintype "passive"))
      (node (ref "J201") (pin "12") (pinfunction "12_12") (pintype "passive"))
      (node (ref "J201") (pin "9") (pinfunction "9_9") (pintype "passive"))
      (node (ref "J202") (pin "3") (pinfunction "3_3") (pintype "passive"))
      (node (ref "J203") (pin "5") (pinfunction "GND_5") (pintype "power_in"))
      (node (ref "R201") (pin "2") (pinfunction "2_2") (pintype "passive"))
      (node (ref "R223") (pin "2") (pinfunction "2_2") (pintype "passive"))
      (node (ref "R225") (pin "1") (pintype "passive"))
      (node (ref "R227") (pin "2") (pinfunction "2_2") (pintype "passive"))
      (node (ref "U200") (pin "1") (pinfunction "GND_1") (pintype "power_in"))
      (node (ref "U200") (pin "15") (pinfunction "GND_15") (pintype "power_in"))
      (node (ref "U200") (pin "38") (pinfunction "GND_38") (pintype "power_in"))
      (node (ref "U201") (pin "29") (pinfunction "PGND_29") (pintype "passive"))
      (node (ref "U201") (pin "3") (pinfunction "GND_3") (pintype "power_in"))
      (node (ref "U202") (pin "4") (pinfunction "GND_4") (pintype "power_in"))
    )
    (net (code "43") (name "Net-(B200-Pad2)") (class "Default")
      (node (ref "B200") (pin "2") (pinfunction "2_2") (pintype "passive"))
      (node (ref "C208") (pin "1") (pintype "passive"))
    )
    (net (code "44") (name "Net-(C200-Pad1)") (class "Default")
      (node (ref "C200") (pin "1") (pintype "passive"))
      (node (ref "D201") (pin "1") (pinfunction "1_1") (pintype "passive"))
      (node (ref "J201") (pin "4") (pinfunction "4_4") (pintype "passive"))
      (node (ref "R202") (pin "2") (pinfunction "2_2") (pintype "passive"))
    )
    (net (code "45") (name "Net-(D202-ANODE)") (class "Default")
      (node (ref "D202") (pin "2") (pinfunction "ANODE_2") (pintype "passive"))
      (node (ref "R206") (pin "1") (pinfunction "1_1") (pintype "passive"))
      (node (ref "R212") (pin "1") (pintype "passive"))
      (node (ref "TP200") (pin "1") (pintype "passive"))
    )
    (net (code "46") (name "Net-(D205-ANODE)") (class "Default")
      (node (ref "D205") (pin "2") (pinfunction "ANODE_2") (pintype "passive"))
      (node (ref "R209") (pin "1") (pinfunction "1_1") (pintype "passive"))
      (node (ref "R218") (pin "1") (pintype "passive"))
      (node (ref "R223") (pin "1") (pinfunction "1_1") (pintype "passive"))
      (node (ref "TP203") (pin "1") (pintype "passive"))
    )
    (net (code "47") (name "Net-(D208-C1-Pad4)") (class "Default")
      (node (ref "D208") (pin "4") (pinfunction "C1_4") (pintype "passive"))
      (node (ref "R215") (pin "2") (pintype "passive"))
    )
    (net (code "48") (name "Net-(D208-C1-Pad5)") (class "Default")
      (node (ref "D208") (pin "5") (pinfunction "C1_5") (pintype "passive"))
      (node (ref "R216") (pin "2") (pintype "passive"))
    )
    (net (code "49") (name "Net-(D208-C1-Pad6)") (class "Default")
      (node (ref "D208") (pin "6") (pinfunction "C1_6") (pintype "passive"))
      (node (ref "R217") (pin "2") (pintype "passive"))
    )
    (net (code "50") (name "Net-(J201-Pad1)") (class "Default")
      (node (ref "J201") (pin "1") (pinfunction "1_1") (pintype "passive"))
      (node (ref "R211") (pin "2") (pinfunction "2_2") (pintype "passive"))
    )
    (net (code "51") (name "Net-(J201-Pad2)") (class "Default")
      (node (ref "J201") (pin "2") (pinfunction "2_2") (pintype "passive"))
      (node (ref "R210") (pin "2") (pinfunction "2_2") (pintype "passive"))
    )
    (net (code "52") (name "Net-(J201-Pad3)") (class "Default")
      (node (ref "J201") (pin "3") (pinfunction "3_3") (pintype "passive"))
      (node (ref "R209") (pin "2") (pinfunction "2_2") (pintype "passive"))
    )
    (net (code "53") (name "Net-(J201-Pad5)") (class "Default")
      (node (ref "J201") (pin "5") (pinfunction "5_5") (pintype "passive"))
      (node (ref "R208") (pin "2") (pinfunction "2_2") (pintype "passive"))
    )
    (net (code "54") (name "Net-(J201-Pad6)") (class "Default")
      (node (ref "J201") (pin "6") (pinfunction "6_6") (pintype "passive"))
      (node (ref "R201") (pin "1") (pinfunction "1_1") (pintype "passive"))
    )
    (net (code "55") (name "Net-(J201-Pad7)") (class "Default")
      (node (ref "J201") (pin "7") (pinfunction "7_7") (pintype "passive"))
      (node (ref "R207") (pin "2") (pinfunction "2_2") (pintype "passive"))
    )
    (net (code "56") (name "Net-(J201-Pad8)") (class "Default")
      (node (ref "J201") (pin "8") (pinfunction "8_8") (pintype "passive"))
      (node (ref "R206") (pin "2") (pinfunction "2_2") (pintype "passive"))
    )
    (net (code "57") (name "Net-(Q200-B)") (class "Default")
      (node (ref "Q200") (pin "1") (pinfunction "B_1") (pintype "passive"))
      (node (ref "R228") (pin "1") (pinfunction "1_1") (pintype "passive"))
    )
    (net (code "58") (name "Net-(Q201-B)") (class "Default")
      (node (ref "Q201") (pin "1") (pinfunction "B_1") (pintype "passive"))
      (node (ref "R229") (pin "1") (pinfunction "1_1") (pintype "passive"))
    )
    (net (code "59") (name "Net-(U201-VBUS)") (class "Default")
      (node (ref "R224") (pin "2") (pintype "passive"))
      (node (ref "R225") (pin "2") (pintype "passive"))
      (node (ref "U201") (pin "8") (pinfunction "VBUS_8") (pintype "passive"))
    )
    (net (code "60") (name "Net-(U201-~{RST})") (class "Default")
      (node (ref "R226") (pin "2") (pintype "passive"))
      (node (ref "U201") (pin "9") (pinfunction "~{RST}_9") (pintype "passive"))
    )
    (net (code "61") (name "Net-(U201-~{SUSPEND})") (class "Default")
      (node (ref "R227") (pin "1") (pinfunction "1_1") (pintype "passive"))
      (node (ref "U201") (pin "11") (pinfunction "~{SUSPEND}_11") (pintype "passive"))
    )
    (net (code "62") (name "V_USB") (class "Default")
      (node (ref "C207") (pin "2") (pintype "passive"))
      (node (ref "C209") (pin "1") (pintype "passive"))
      (node (ref "J203") (pin "1") (pinfunction "VCC_1") (pintype "power_in"))
      (node (ref "R224") (pin "1") (pintype "passive"))
      (node (ref "U202") (pin "6") (pinfunction "VBUS_6") (pintype "passive"))
    )
    (net (code "63") (name "unconnected-(B200-Pad4)") (class "Default")
      (node (ref "B200") (pin "4") (pinfunction "4_4") (pintype "passive"))
    )
    (net (code "64") (name "unconnected-(B201-Pad2)") (class "Default")
      (node (ref "B201") (pin "2") (pinfunction "2_2") (pintype "passive"))
    )
    (net (code "65") (name "unconnected-(B201-Pad4)") (class "Default")
      (node (ref "B201") (pin "4") (pinfunction "4_4") (pintype "passive"))
    )
    (net (code "66") (name "unconnected-(J203-ID-Pad4)") (class "Default")
      (node (ref "J203") (pin "4") (pinfunction "ID_4") (pintype "passive+no_connect"))
    )
    (net (code "67") (name "unconnected-(R215-Pad1)") (class "Default")
      (node (ref "R215") (pin "1") (pintype "passive+no_connect"))
    )
    (net (code "68") (name "unconnected-(U200-NC-Pad32)") (class "Default")
      (node (ref "U200") (pin "32") (pinfunction "NC_32") (pintype "passive+no_connect"))
    )
    (net (code "69") (name "unconnected-(U200-SCK{slash}CLK-Pad20)") (class "Default")
      (node (ref "U200") (pin "20") (pinfunction "SCK/CLK_20") (pintype "bidirectional+no_connect"))
    )
    (net (code "70") (name "unconnected-(U200-SCS{slash}CMD-Pad19)") (class "Default")
      (node (ref "U200") (pin "19") (pinfunction "SCS/CMD_19") (pintype "bidirectional+no_connect"))
    )
    (net (code "71") (name "unconnected-(U200-SDI{slash}SD1-Pad22)") (class "Default")
      (node (ref "U200") (pin "22") (pinfunction "SDI/SD1_22") (pintype "bidirectional+no_connect"))
    )
    (net (code "72") (name "unconnected-(U200-SDO{slash}SD0-Pad21)") (class "Default")
      (node (ref "U200") (pin "21") (pinfunction "SDO/SD0_21") (pintype "bidirectional+no_connect"))
    )
    (net (code "73") (name "unconnected-(U200-SENSOR_VN-Pad5)") (class "Default")
      (node (ref "U200") (pin "5") (pinfunction "SENSOR_VN_5") (pintype "passive"))
    )
    (net (code "74") (name "unconnected-(U200-SENSOR_VP-Pad4)") (class "Default")
      (node (ref "U200") (pin "4") (pinfunction "SENSOR_VP_4") (pintype "passive"))
    )
    (net (code "75") (name "unconnected-(U200-SHD{slash}SD2-Pad17)") (class "Default")
      (node (ref "U200") (pin "17") (pinfunction "SHD/SD2_17") (pintype "bidirectional+no_connect"))
    )
    (net (code "76") (name "unconnected-(U200-SWP{slash}SD3-Pad18)") (class "Default")
      (node (ref "U200") (pin "18") (pinfunction "SWP/SD3_18") (pintype "bidirectional+no_connect"))
    )
    (net (code "77") (name "unconnected-(U201-CHR0-Pad15)") (class "Default")
      (node (ref "U201") (pin "15") (pinfunction "CHR0_15") (pintype "passive+no_connect"))
    )
    (net (code "78") (name "unconnected-(U201-CHR1-Pad14)") (class "Default")
      (node (ref "U201") (pin "14") (pinfunction "CHR1_14") (pintype "passive+no_connect"))
    )
    (net (code "79") (name "unconnected-(U201-CHREN-Pad13)") (class "Default")
      (node (ref "U201") (pin "13") (pinfunction "CHREN_13") (pintype "passive+no_connect"))
    )
    (net (code "80") (name "unconnected-(U201-IO0-Pad19)") (class "Default")
      (node (ref "U201") (pin "19") (pinfunction "IO0_19") (pintype "passive+no_connect"))
    )
    (net (code "81") (name "unconnected-(U201-IO1-Pad18)") (class "Default")
      (node (ref "U201") (pin "18") (pinfunction "IO1_18") (pintype "passive+no_connect"))
    )
    (net (code "82") (name "unconnected-(U201-IO2-Pad17)") (class "Default")
      (node (ref "U201") (pin "17") (pinfunction "IO2_17") (pintype "passive+no_connect"))
    )
    (net (code "83") (name "unconnected-(U201-IO3-Pad16)") (class "Default")
      (node (ref "U201") (pin "16") (pinfunction "IO3_16") (pintype "passive+no_connect"))
    )
    (net (code "84") (name "unconnected-(U201-IO4-Pad22)") (class "Default")
      (node (ref "U201") (pin "22") (pinfunction "IO4_22") (pintype "passive+no_connect"))
    )
    (net (code "85") (name "unconnected-(U201-IO5-Pad21)") (class "Default")
      (node (ref "U201") (pin "21") (pinfunction "IO5_21") (pintype "passive+no_connect"))
    )
    (net (code "86") (name "unconnected-(U201-IO6-Pad20)") (class "Default")
      (node (ref "U201") (pin "20") (pinfunction "IO6_20") (pintype "passive+no_connect"))
    )
    (net (code "87") (name "unconnected-(U201-NC-Pad10)") (class "Default")
      (node (ref "U201") (pin "10") (pinfunction "NC_10") (pintype "passive+no_connect"))
    )
    (net (code "88") (name "unconnected-(U201-SUSPEND-Pad12)") (class "Default")
      (node (ref "U201") (pin "12") (pinfunction "SUSPEND_12") (pintype "passive+no_connect"))
    )
    (net (code "89") (name "unconnected-(U202-ID-Pad3)") (class "Default")
      (node (ref "U202") (pin "3") (pinfunction "ID_3") (pintype "passive"))
    )
    (net (code "90") (name "unconnected-(U202-NC-Pad5)") (class "Default")
      (node (ref "U202") (pin "5") (pinfunction "NC_5") (pintype "passive"))
    )
  )
)
